# Sheet1.net
KiCad netlist of a schematic drawn in Altium Designer
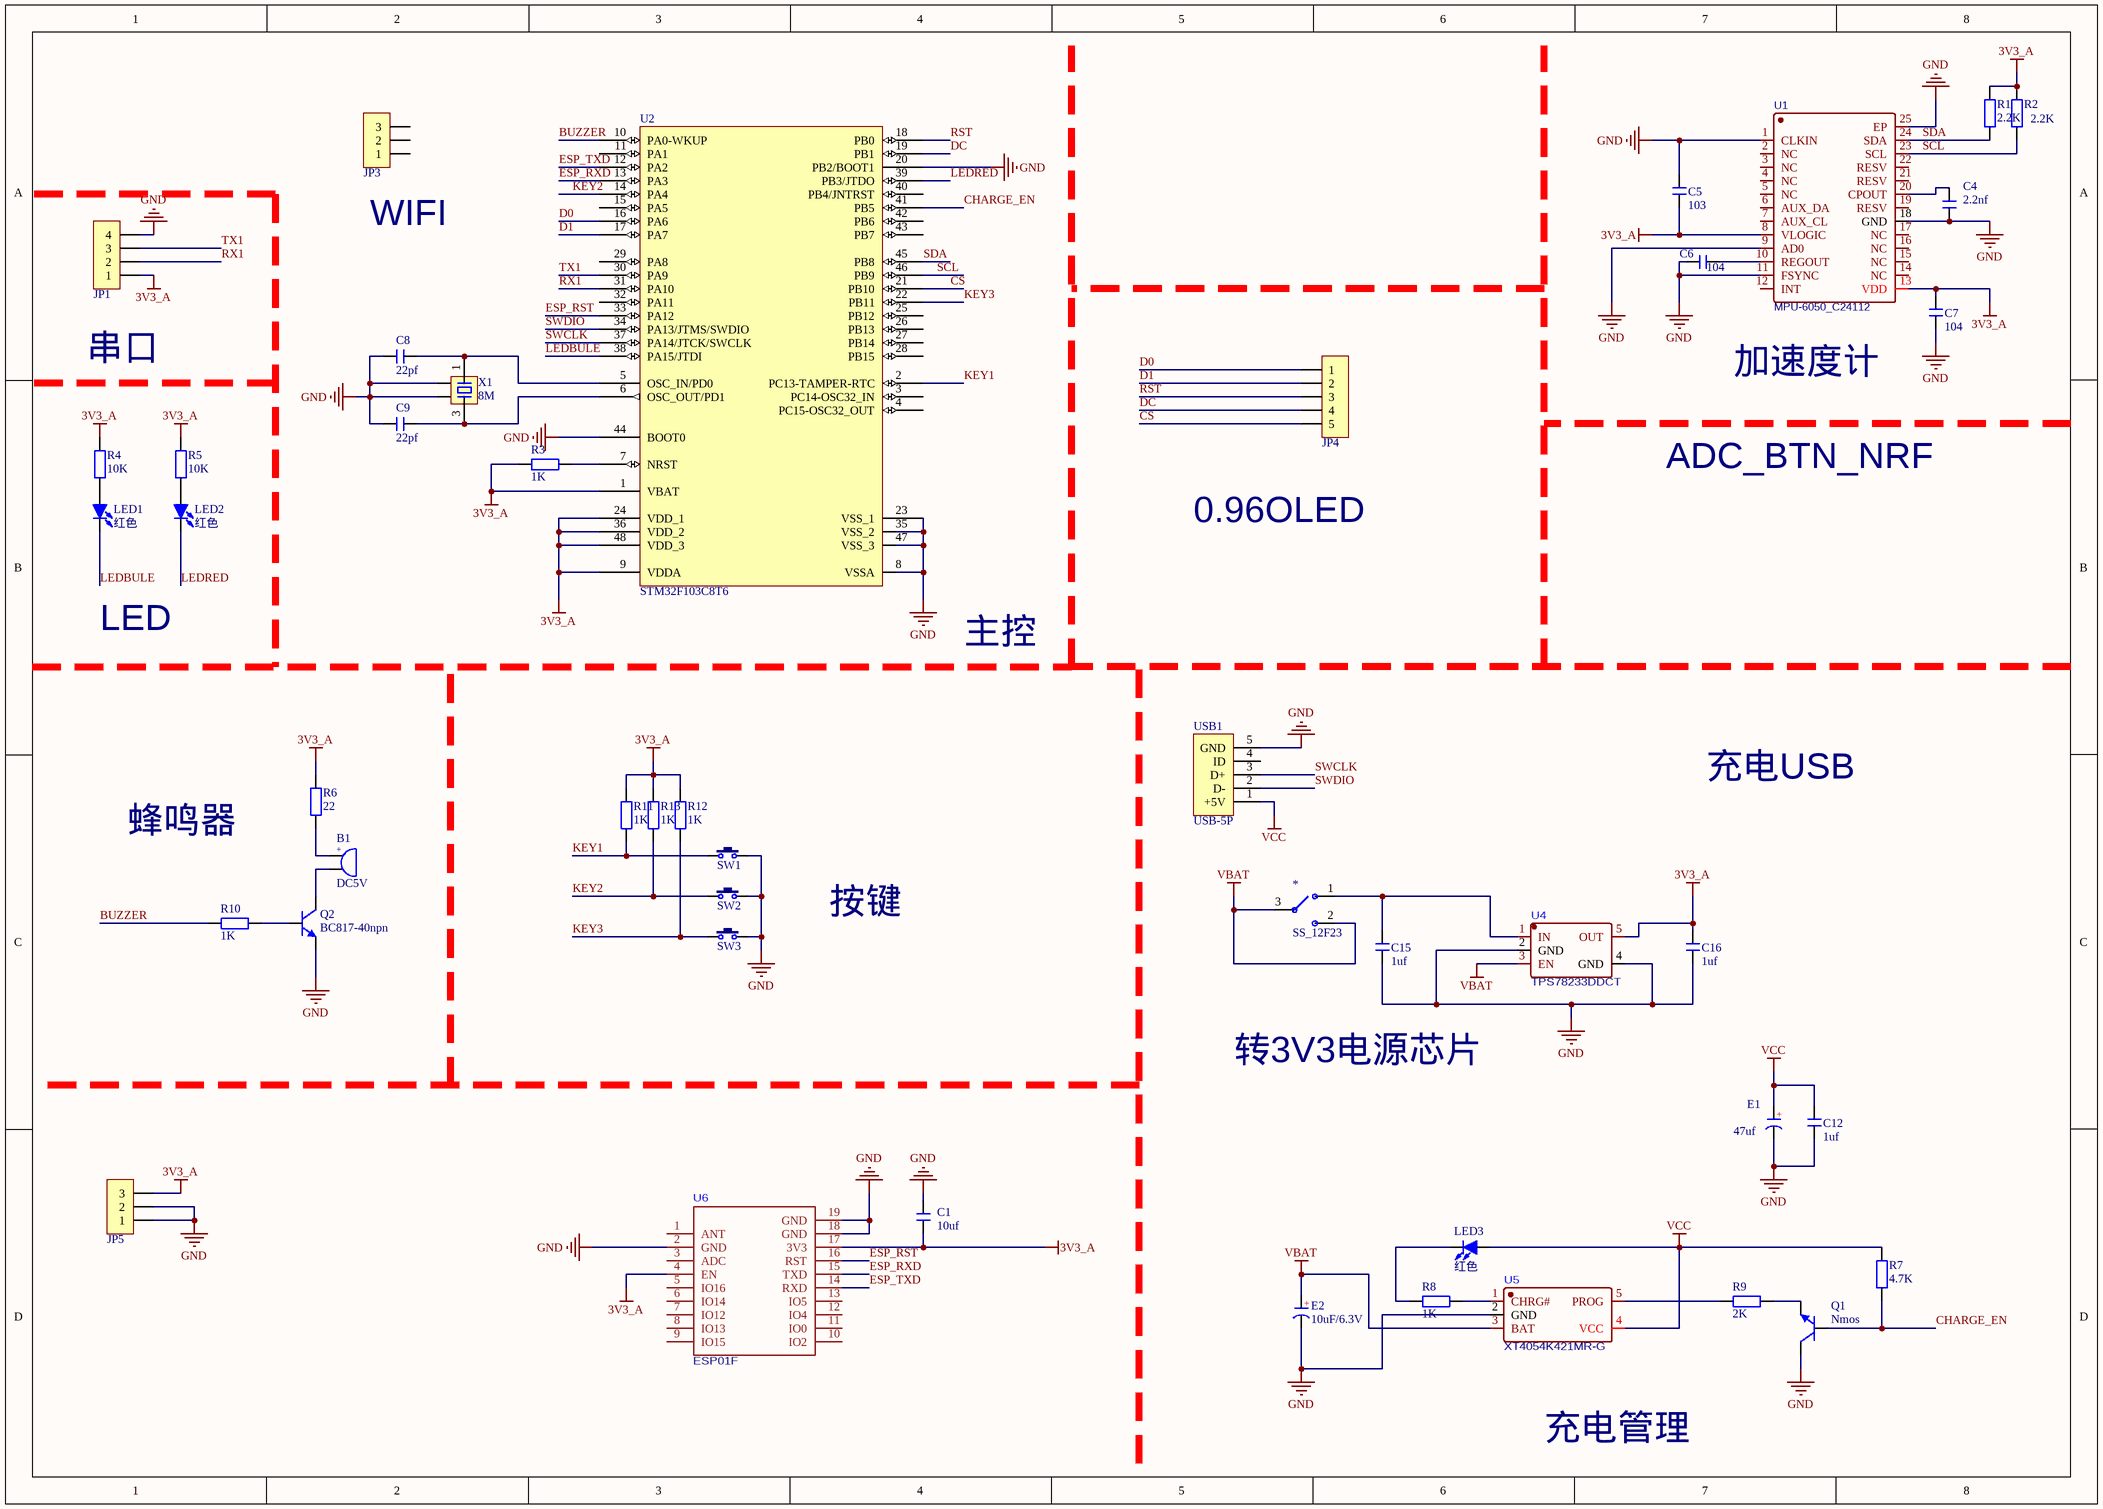
[diagram p0: Sheet1.SchDoc]

(export (version "E")
  (design (tool "Eeschema 10.0.6"))
  (components
    (comp (ref "*") (value "SS_12F23") (footprint "SS_12F23") (libsource (lib "Schlib1") (part "SS_12F23")))
    (comp (ref "B1")
      (value "DC5V")
      (footprint "蜂鸣器5020")
      (description "蜂鸣器")
      (fields (field (name "版权归属") "黎明电子style"))
      (libsource (lib "未分类器件") (part "BEEP"))
    )
    (comp (ref "C1")
      (value "10uf")
      (footprint "C 0805")
      (description "无极性贴片电容")
      (fields (field (name "版权归属") "黎明电子style"))
      (libsource (lib "电阻-电容-电感") (part "C"))
    )
    (comp (ref "C4")
      (value "2.2nf")
      (footprint "C 0603")
      (description "无极性贴片电容")
      (fields (field (name "版权归属") "黎明电子style"))
      (libsource (lib "电阻-电容-电感") (part "C"))
    )
    (comp (ref "C5")
      (value "103")
      (footprint "C 0603")
      (description "无极性贴片电容")
      (fields (field (name "版权归属") "黎明电子style"))
      (libsource (lib "电阻-电容-电感") (part "C"))
    )
    (comp (ref "C6")
      (value "104")
      (footprint "C 0603")
      (description "无极性贴片电容")
      (fields (field (name "版权归属") "黎明电子style"))
      (libsource (lib "电阻-电容-电感") (part "C"))
    )
    (comp (ref "C7")
      (value "104")
      (footprint "C 0603")
      (description "无极性贴片电容")
      (fields (field (name "版权归属") "黎明电子style"))
      (libsource (lib "电阻-电容-电感") (part "C"))
    )
    (comp (ref "C8")
      (value "22pf")
      (footprint "C 0603")
      (description "无极性贴片电容")
      (fields (field (name "版权归属") "黎明电子style"))
      (libsource (lib "电阻-电容-电感") (part "C"))
    )
    (comp (ref "C9")
      (value "22pf")
      (footprint "C 0603")
      (description "无极性贴片电容")
      (fields (field (name "版权归属") "黎明电子style"))
      (libsource (lib "电阻-电容-电感") (part "C"))
    )
    (comp (ref "C12")
      (value "1uf")
      (footprint "C 0603")
      (description "无极性贴片电容")
      (fields (field (name "版权归属") "黎明电子style"))
      (libsource (lib "电阻-电容-电感") (part "C"))
    )
    (comp (ref "C15")
      (value "1uf")
      (footprint "C 0603")
      (description "无极性贴片电容")
      (fields (field (name "版权归属") "黎明电子style"))
      (libsource (lib "电阻-电容-电感") (part "C"))
    )
    (comp (ref "C16")
      (value "1uf")
      (footprint "C 0603")
      (description "无极性贴片电容")
      (fields (field (name "版权归属") "黎明电子style"))
      (libsource (lib "电阻-电容-电感") (part "C"))
    )
    (comp (ref "E1")
      (value "47uf")
      (footprint "CD A(3216)")
      (description "贴片钽电容")
      (fields (field (name "版权归属") "黎明电子style"))
      (libsource (lib "电阻-电容-电感") (part "C-CD"))
    )
    (comp (ref "E2")
      (value "10uF/6.3V")
      (footprint "CD A(3216)")
      (description "贴片钽电容")
      (fields (field (name "版权归属") "黎明电子style"))
      (libsource (lib "电阻-电容-电感") (part "C-CD"))
    )
    (comp (ref "JP1")
      (value "HDR-1X4")
      (footprint "uart_pin")
      (description "4P接插件")
      (fields (field (name "版权归属") "黎明电子style"))
      (libsource (lib "接插件") (part "Header 4"))
    )
    (comp (ref "JP3")
      (value "HDR-1X3")
      (footprint "OLED_3PIN")
      (description "3P接插件")
      (fields (field (name "版权归属") "黎明电子style"))
      (libsource (lib "接插件") (part "Header 3"))
    )
    (comp (ref "JP4")
      (value "HDR-1X5")
      (footprint "OLED_5PIN")
      (description "5P接插件")
      (fields (field (name "版权归属") "黎明电子style"))
      (libsource (lib "接插件") (part "Header 5"))
    )
    (comp (ref "JP5")
      (value "HDR-1X3")
      (footprint "OLED_3PIN")
      (description "3P接插件")
      (fields (field (name "版权归属") "黎明电子style"))
      (libsource (lib "接插件") (part "Header 3"))
    )
    (comp (ref "LED1")
      (value "红色")
      (footprint "LED 0603G")
      (description "贴片LED")
      (fields (field (name "版权归属") "黎明电子style"))
      (libsource (lib "LED") (part "LED-SMD"))
    )
    (comp (ref "LED2")
      (value "红色")
      (footprint "LED 0603G")
      (description "贴片LED")
      (fields (field (name "版权归属") "黎明电子style"))
      (libsource (lib "LED") (part "LED-SMD"))
    )
    (comp (ref "LED3")
      (value "红色")
      (footprint "LED 0603G")
      (description "贴片LED")
      (fields (field (name "版权归属") "黎明电子style"))
      (libsource (lib "LED") (part "LED-SMD"))
    )
    (comp (ref "Q1")
      (value "Nmos")
      (footprint "NMOS")
      (description "低频放大-NPN型")
      (fields (field (name "版权归属") "黎明电子style"))
      (libsource (lib "三极管") (part "9013-SMD"))
    )
    (comp (ref "Q2")
      (value "BC817-40npn")
      (footprint "SOT23-3N")
      (description "高频放大-NPN型")
      (fields (field (name "版权归属") "黎明电子style"))
      (libsource (lib "三极管") (part "8050-SMD"))
    )
    (comp (ref "R1")
      (value "2.2K")
      (footprint "R 0603")
      (description "贴片电阻")
      (fields (field (name "版权归属") "黎明电子style"))
      (libsource (lib "电阻-电容-电感") (part "R"))
    )
    (comp (ref "R2")
      (value "2.2K")
      (footprint "R 0603")
      (description "贴片电阻")
      (fields (field (name "版权归属") "黎明电子style"))
      (libsource (lib "电阻-电容-电感") (part "R"))
    )
    (comp (ref "R3")
      (value "1K")
      (footprint "R 0603")
      (description "贴片电阻")
      (fields (field (name "版权归属") "黎明电子style"))
      (libsource (lib "电阻-电容-电感") (part "R"))
    )
    (comp (ref "R4")
      (value "10K")
      (footprint "R 0603")
      (description "贴片电阻")
      (fields (field (name "版权归属") "黎明电子style"))
      (libsource (lib "电阻-电容-电感") (part "R"))
    )
    (comp (ref "R5")
      (value "10K")
      (footprint "R 0603")
      (description "贴片电阻")
      (fields (field (name "版权归属") "黎明电子style"))
      (libsource (lib "电阻-电容-电感") (part "R"))
    )
    (comp (ref "R6")
      (value "22")
      (footprint "R 0603")
      (description "贴片电阻")
      (fields (field (name "版权归属") "黎明电子style"))
      (libsource (lib "电阻-电容-电感") (part "R"))
    )
    (comp (ref "R7")
      (value "4.7K")
      (footprint "R 0603")
      (description "贴片电阻")
      (fields (field (name "版权归属") "黎明电子style"))
      (libsource (lib "电阻-电容-电感") (part "R"))
    )
    (comp (ref "R8")
      (value "1K")
      (footprint "R 0603")
      (description "贴片电阻")
      (fields (field (name "版权归属") "黎明电子style"))
      (libsource (lib "电阻-电容-电感") (part "R"))
    )
    (comp (ref "R9")
      (value "2K")
      (footprint "R 0603")
      (description "贴片电阻")
      (fields (field (name "版权归属") "黎明电子style"))
      (libsource (lib "电阻-电容-电感") (part "R"))
    )
    (comp (ref "R10")
      (value "1K")
      (footprint "R 0603")
      (description "贴片电阻")
      (fields (field (name "版权归属") "黎明电子style"))
      (libsource (lib "电阻-电容-电感") (part "R"))
    )
    (comp (ref "R11")
      (value "1K")
      (footprint "R 0603")
      (description "贴片电阻")
      (fields (field (name "版权归属") "黎明电子style"))
      (libsource (lib "电阻-电容-电感") (part "R"))
    )
    (comp (ref "R12")
      (value "1K")
      (footprint "R 0603")
      (description "贴片电阻")
      (fields (field (name "版权归属") "黎明电子style"))
      (libsource (lib "电阻-电容-电感") (part "R"))
    )
    (comp (ref "R13")
      (value "1K")
      (footprint "R 0603")
      (description "贴片电阻")
      (fields (field (name "版权归属") "黎明电子style"))
      (libsource (lib "电阻-电容-电感") (part "R"))
    )
    (comp (ref "SW1")
      (value "3x6x5")
      (footprint "SB-2*4*3.5")
      (description "3x6轻触开关")
      (fields (field (name "版权归属") "黎明电子style"))
      (libsource (lib "按键-开关") (part "TSW 3x6"))
    )
    (comp (ref "SW2")
      (value "3x6x5")
      (footprint "SB-2*4*3.5")
      (description "3x6轻触开关")
      (fields (field (name "版权归属") "黎明电子style"))
      (libsource (lib "按键-开关") (part "TSW 3x6"))
    )
    (comp (ref "SW3")
      (value "3x6x5")
      (footprint "SB-2*4*3.5")
      (description "3x6轻触开关")
      (fields (field (name "版权归属") "黎明电子style"))
      (libsource (lib "按键-开关") (part "TSW 3x6"))
    )
    (comp (ref "U1")
      (value "MPU-6050_C24112")
      (footprint "MPU6050")
      (fields (field (name "BOM_MANUFACTURER PART") "MPU-6050") (field (name "BOM_SUPPLIER PART") "C24112"))
      (libsource (lib "PCB_Project") (part "MPU-6050_C24112"))
    )
    (comp (ref "U2")
      (value "STM32F103C8T6")
      (footprint "LQFP48 7X7_M")
      (description "Flaah:64/RAM:20/IO:36")
      (fields (field (name "版权归属") "黎明电子style"))
      (libsource (lib "STM32系列单片机") (part "STM32F103C8T6"))
    )
    (comp (ref "U4")
      (value "TPS78233DDCT")
      (footprint "SOT-23-5_L3.0-W1.7-P0.95-LS2.8-BR")
      (libsource (lib "Schlib1") (part "TPS78233DDCT"))
    )
    (comp (ref "U5")
      (value "XT4054K421MR-G")
      (footprint "SOT-23-5_L3.0-W1.7-P0.95-LS2.8-BR")
      (libsource (lib "Schlib1") (part "XT4054K421MR-G"))
    )
    (comp (ref "U6") (value "ESP01F") (footprint "ESP-01F") (libsource (lib "Schlib1") (part "ESP01F")))
    (comp (ref "USB1")
      (value "USB-5P")
      (footprint "MICRO-USB")
      (description "微型USB母座")
      (fields (field (name "版权归属") "黎明电子style"))
      (libsource (lib "接口类") (part "USB-5P"))
    )
    (comp (ref "X1")
      (value "8M")
      (footprint "OSC-SMD_4P-L3.2-W2.5-BL")
      (description "4脚晶振")
      (fields (field (name "版权归属") "源创客"))
      (libsource (lib "Schlib1") (part "XTAL-4"))
    )
  )
  (nets
    (net (code "1") (name "/BUZZER") (class "Default")
      (node (ref "R10") (pin "2") (pinfunction "2_2") (pintype "passive"))
      (node (ref "U2") (pin "10") (pinfunction "PA0-WKUP_10") (pintype "bidirectional"))
    )
    (net (code "2") (name "/CHARGE_EN") (class "Default")
      (node (ref "Q1") (pin "1") (pinfunction "B_1") (pintype "passive"))
      (node (ref "R7") (pin "2") (pinfunction "2_2") (pintype "passive"))
      (node (ref "U2") (pin "41") (pinfunction "PB5_41") (pintype "bidirectional"))
    )
    (net (code "3") (name "/CS") (class "Default")
      (node (ref "JP4") (pin "5") (pinfunction "5_5") (pintype "passive"))
      (node (ref "U2") (pin "21") (pinfunction "PB10_21") (pintype "bidirectional"))
    )
    (net (code "4") (name "/D0") (class "Default")
      (node (ref "JP4") (pin "1") (pinfunction "1_1") (pintype "passive"))
      (node (ref "U2") (pin "16") (pinfunction "PA6_16") (pintype "bidirectional"))
    )
    (net (code "5") (name "/D1") (class "Default")
      (node (ref "JP4") (pin "2") (pinfunction "2_2") (pintype "passive"))
      (node (ref "U2") (pin "17") (pinfunction "PA7_17") (pintype "bidirectional"))
    )
    (net (code "6") (name "/DC") (class "Default")
      (node (ref "JP4") (pin "4") (pinfunction "4_4") (pintype "passive"))
      (node (ref "U2") (pin "19") (pinfunction "PB1_19") (pintype "bidirectional"))
    )
    (net (code "7") (name "/ESP_RST") (class "Default")
      (node (ref "U2") (pin "33") (pinfunction "PA12_33") (pintype "bidirectional"))
      (node (ref "U6") (pin "16") (pinfunction "RST_16") (pintype "passive"))
    )
    (net (code "8") (name "/ESP_RXD") (class "Default")
      (node (ref "U2") (pin "13") (pinfunction "PA3_13") (pintype "bidirectional"))
      (node (ref "U6") (pin "15") (pinfunction "TXD_15") (pintype "passive"))
    )
    (net (code "9") (name "/ESP_TXD") (class "Default")
      (node (ref "U2") (pin "12") (pinfunction "PA2_12") (pintype "bidirectional"))
      (node (ref "U6") (pin "14") (pinfunction "RXD_14") (pintype "passive"))
    )
    (net (code "10") (name "/KEY1") (class "Default")
      (node (ref "R11") (pin "2") (pinfunction "2_2") (pintype "passive"))
      (node (ref "SW1") (pin "1") (pinfunction "1_1") (pintype "passive"))
      (node (ref "U2") (pin "2") (pinfunction "PC13-TAMPER-RTC_2") (pintype "bidirectional"))
    )
    (net (code "11") (name "/KEY2") (class "Default")
      (node (ref "R13") (pin "2") (pinfunction "2_2") (pintype "passive"))
      (node (ref "SW2") (pin "1") (pinfunction "1_1") (pintype "passive"))
      (node (ref "U2") (pin "14") (pinfunction "PA4_14") (pintype "bidirectional"))
    )
    (net (code "12") (name "/KEY3") (class "Default")
      (node (ref "R12") (pin "2") (pinfunction "2_2") (pintype "passive"))
      (node (ref "SW3") (pin "1") (pinfunction "1_1") (pintype "passive"))
      (node (ref "U2") (pin "22") (pinfunction "PB11_22") (pintype "bidirectional"))
    )
    (net (code "13") (name "/LEDBULE") (class "Default")
      (node (ref "LED1") (pin "2") (pinfunction "K_2") (pintype "passive"))
      (node (ref "U2") (pin "38") (pinfunction "PA15/JTDI_38") (pintype "bidirectional"))
    )
    (net (code "14") (name "/LEDRED") (class "Default")
      (node (ref "LED2") (pin "2") (pinfunction "K_2") (pintype "passive"))
      (node (ref "U2") (pin "39") (pinfunction "PB3/JTDO_39") (pintype "bidirectional"))
    )
    (net (code "15") (name "/RST") (class "Default")
      (node (ref "JP4") (pin "3") (pinfunction "3_3") (pintype "passive"))
      (node (ref "U2") (pin "18") (pinfunction "PB0_18") (pintype "bidirectional"))
    )
    (net (code "16") (name "/RX1") (class "Default")
      (node (ref "JP1") (pin "2") (pinfunction "2_2") (pintype "passive"))
      (node (ref "U2") (pin "31") (pinfunction "PA10_31") (pintype "bidirectional"))
    )
    (net (code "17") (name "/SCL") (class "Default")
      (node (ref "R2") (pin "1") (pinfunction "1_1") (pintype "passive"))
      (node (ref "U1") (pin "23") (pinfunction "SCL_23") (pintype "passive"))
      (node (ref "U2") (pin "46") (pinfunction "PB9_46") (pintype "bidirectional"))
    )
    (net (code "18") (name "/SDA") (class "Default")
      (node (ref "R1") (pin "1") (pinfunction "1_1") (pintype "passive"))
      (node (ref "U1") (pin "24") (pinfunction "SDA_24") (pintype "passive"))
      (node (ref "U2") (pin "45") (pinfunction "PB8_45") (pintype "bidirectional"))
    )
    (net (code "19") (name "/SWCLK") (class "Default")
      (node (ref "U2") (pin "37") (pinfunction "PA14/JTCK/SWCLK_37") (pintype "bidirectional"))
      (node (ref "USB1") (pin "3") (pinfunction "D+_3") (pintype "passive"))
    )
    (net (code "20") (name "/SWDIO") (class "Default")
      (node (ref "U2") (pin "34") (pinfunction "PA13/JTMS/SWDIO_34") (pintype "bidirectional"))
      (node (ref "USB1") (pin "2") (pinfunction "D-_2") (pintype "passive"))
    )
    (net (code "21") (name "/TX1") (class "Default")
      (node (ref "JP1") (pin "3") (pinfunction "3_3") (pintype "passive"))
      (node (ref "U2") (pin "30") (pinfunction "PA9_30") (pintype "bidirectional"))
    )
    (net (code "22") (name "3V3_A") (class "Default")
      (node (ref "C1") (pin "1") (pinfunction "1_1") (pintype "passive"))
      (node (ref "C16") (pin "2") (pinfunction "2_2") (pintype "passive"))
      (node (ref "C5") (pin "1") (pinfunction "1_1") (pintype "passive"))
      (node (ref "C7") (pin "2") (pinfunction "2_2") (pintype "passive"))
      (node (ref "JP1") (pin "1") (pinfunction "1_1") (pintype "passive"))
      (node (ref "JP5") (pin "3") (pinfunction "3_3") (pintype "passive"))
      (node (ref "R1") (pin "2") (pinfunction "2_2") (pintype "passive"))
      (node (ref "R11") (pin "1") (pinfunction "1_1") (pintype "passive"))
      (node (ref "R12") (pin "1") (pinfunction "1_1") (pintype "passive"))
      (node (ref "R13") (pin "1") (pinfunction "1_1") (pintype "passive"))
      (node (ref "R2") (pin "2") (pinfunction "2_2") (pintype "passive"))
      (node (ref "R3") (pin "2") (pinfunction "2_2") (pintype "passive"))
      (node (ref "R4") (pin "2") (pinfunction "2_2") (pintype "passive"))
      (node (ref "R5") (pin "2") (pinfunction "2_2") (pintype "passive"))
      (node (ref "R6") (pin "2") (pinfunction "2_2") (pintype "passive"))
      (node (ref "U1") (pin "13") (pinfunction "VDD_13") (pintype "passive"))
      (node (ref "U1") (pin "8") (pinfunction "VLOGIC_8") (pintype "passive"))
      (node (ref "U2") (pin "1") (pinfunction "VBAT_1") (pintype "power_in"))
      (node (ref "U2") (pin "24") (pinfunction "VDD_1_24") (pintype "power_in"))
      (node (ref "U2") (pin "36") (pinfunction "VDD_2_36") (pintype "power_in"))
      (node (ref "U2") (pin "48") (pinfunction "VDD_3_48") (pintype "power_in"))
      (node (ref "U2") (pin "9") (pinfunction "VDDA_9") (pintype "power_in"))
      (node (ref "U4") (pin "5") (pinfunction "OUT_5") (pintype "passive"))
      (node (ref "U6") (pin "17") (pinfunction "3V3_17") (pintype "passive"))
      (node (ref "U6") (pin "4") (pinfunction "EN_4") (pintype "passive"))
    )
    (net (code "23") (name "GND") (class "Default")
      (node (ref "C1") (pin "2") (pinfunction "2_2") (pintype "passive"))
      (node (ref "C12") (pin "1") (pinfunction "1_1") (pintype "passive"))
      (node (ref "C15") (pin "1") (pinfunction "1_1") (pintype "passive"))
      (node (ref "C16") (pin "1") (pinfunction "1_1") (pintype "passive"))
      (node (ref "C4") (pin "2") (pinfunction "2_2") (pintype "passive"))
      (node (ref "C5") (pin "2") (pinfunction "2_2") (pintype "passive"))
      (node (ref "C6") (pin "1") (pinfunction "1_1") (pintype "passive"))
      (node (ref "C7") (pin "1") (pinfunction "1_1") (pintype "passive"))
      (node (ref "C8") (pin "1") (pinfunction "1_1") (pintype "passive"))
      (node (ref "C9") (pin "1") (pinfunction "1_1") (pintype "passive"))
      (node (ref "E1") (pin "2") (pinfunction "K_2") (pintype "passive"))
      (node (ref "E2") (pin "2") (pinfunction "K_2") (pintype "passive"))
      (node (ref "JP1") (pin "4") (pinfunction "4_4") (pintype "passive"))
      (node (ref "JP5") (pin "1") (pinfunction "1_1") (pintype "passive"))
      (node (ref "JP5") (pin "2") (pinfunction "2_2") (pintype "passive"))
      (node (ref "Q1") (pin "3") (pinfunction "C_3") (pintype "passive"))
      (node (ref "Q2") (pin "2") (pinfunction "E_2") (pintype "passive"))
      (node (ref "SW1") (pin "2") (pinfunction "2_2") (pintype "passive"))
      (node (ref "SW2") (pin "2") (pinfunction "2_2") (pintype "passive"))
      (node (ref "SW3") (pin "2") (pinfunction "2_2") (pintype "passive"))
      (node (ref "U1") (pin "1") (pinfunction "CLKIN_1") (pintype "passive"))
      (node (ref "U1") (pin "11") (pinfunction "FSYNC_11") (pintype "passive"))
      (node (ref "U1") (pin "18") (pinfunction "GND_18") (pintype "passive"))
      (node (ref "U1") (pin "25") (pinfunction "EP_25") (pintype "passive"))
      (node (ref "U1") (pin "9") (pinfunction "AD0_9") (pintype "passive"))
      (node (ref "U2") (pin "20") (pinfunction "PB2/BOOT1_20") (pintype "passive"))
      (node (ref "U2") (pin "23") (pinfunction "VSS_1_23") (pintype "power_in"))
      (node (ref "U2") (pin "35") (pinfunction "VSS_2_35") (pintype "power_in"))
      (node (ref "U2") (pin "44") (pinfunction "BOOT0_44") (pintype "passive"))
      (node (ref "U2") (pin "47") (pinfunction "VSS_3_47") (pintype "power_in"))
      (node (ref "U2") (pin "8") (pinfunction "VSSA_8") (pintype "power_in"))
      (node (ref "U4") (pin "2") (pinfunction "GND_2") (pintype "passive"))
      (node (ref "U4") (pin "4") (pinfunction "GND_4") (pintype "passive"))
      (node (ref "U5") (pin "2") (pinfunction "GND_2") (pintype "passive"))
      (node (ref "U6") (pin "18") (pinfunction "GND_18") (pintype "passive"))
      (node (ref "U6") (pin "19") (pinfunction "GND_19") (pintype "passive"))
      (node (ref "U6") (pin "2") (pinfunction "GND_2") (pintype "passive"))
      (node (ref "USB1") (pin "5") (pinfunction "GND_5") (pintype "passive"))
      (node (ref "X1") (pin "2") (pinfunction "2_2") (pintype "passive"))
      (node (ref "X1") (pin "4") (pinfunction "4_4") (pintype "passive"))
    )
    (net (code "24") (name "Net-(B1-Pad1)") (class "Default")
      (node (ref "B1") (pin "1") (pinfunction "1_1") (pintype "passive"))
      (node (ref "R6") (pin "1") (pinfunction "1_1") (pintype "passive"))
    )
    (net (code "25") (name "Net-(LED1-A)") (class "Default")
      (node (ref "LED1") (pin "1") (pinfunction "A_1") (pintype "passive"))
      (node (ref "R4") (pin "1") (pinfunction "1_1") (pintype "passive"))
    )
    (net (code "26") (name "Net-(LED2-A)") (class "Default")
      (node (ref "LED2") (pin "1") (pinfunction "A_1") (pintype "passive"))
      (node (ref "R5") (pin "1") (pinfunction "1_1") (pintype "passive"))
    )
    (net (code "27") (name "Net-(LED3-K)") (class "Default")
      (node (ref "LED3") (pin "2") (pinfunction "K_2") (pintype "passive"))
      (node (ref "R8") (pin "2") (pinfunction "2_2") (pintype "passive"))
    )
    (net (code "28") (name "Net-(Q1-E)") (class "Default")
      (node (ref "Q1") (pin "2") (pinfunction "E_2") (pintype "passive"))
      (node (ref "R9") (pin "1") (pinfunction "1_1") (pintype "passive"))
    )
    (net (code "29") (name "Net-(Q2-B)") (class "Default")
      (node (ref "Q2") (pin "1") (pinfunction "B_1") (pintype "passive"))
      (node (ref "R10") (pin "1") (pinfunction "1_1") (pintype "passive"))
    )
    (net (code "30") (name "Net-(Q2-C)") (class "Default")
      (node (ref "B1") (pin "2") (pinfunction "2_2") (pintype "passive"))
      (node (ref "Q2") (pin "3") (pinfunction "C_3") (pintype "passive"))
    )
    (net (code "31") (name "Net-(U1-CPOUT)") (class "Default")
      (node (ref "C4") (pin "1") (pinfunction "1_1") (pintype "passive"))
      (node (ref "U1") (pin "20") (pinfunction "CPOUT_20") (pintype "passive"))
    )
    (net (code "32") (name "Net-(U1-REGOUT)") (class "Default")
      (node (ref "C6") (pin "2") (pinfunction "2_2") (pintype "passive"))
      (node (ref "U1") (pin "10") (pinfunction "REGOUT_10") (pintype "passive"))
    )
    (net (code "33") (name "Net-(U2-NRST)") (class "Default")
      (node (ref "R3") (pin "1") (pinfunction "1_1") (pintype "passive"))
      (node (ref "U2") (pin "7") (pinfunction "NRST_7") (pintype "bidirectional"))
    )
    (net (code "34") (name "Net-(U2-OSC_IN{slash}PD0)") (class "Default")
      (node (ref "C8") (pin "2") (pinfunction "2_2") (pintype "passive"))
      (node (ref "U2") (pin "5") (pinfunction "OSC_IN/PD0_5") (pintype "passive"))
      (node (ref "X1") (pin "1") (pinfunction "1_1") (pintype "passive"))
    )
    (net (code "35") (name "Net-(U2-OSC_OUT{slash}PD1)") (class "Default")
      (node (ref "C9") (pin "2") (pinfunction "2_2") (pintype "passive"))
      (node (ref "U2") (pin "6") (pinfunction "OSC_OUT/PD1_6") (pintype "output"))
      (node (ref "X1") (pin "3") (pinfunction "3_3") (pintype "passive"))
    )
    (net (code "36") (name "Net-(U4-IN)") (class "Default")
      (node (ref "*") (pin "1") (pinfunction "1_1") (pintype "passive"))
      (node (ref "C15") (pin "2") (pinfunction "2_2") (pintype "passive"))
      (node (ref "U4") (pin "1") (pinfunction "IN_1") (pintype "passive"))
    )
    (net (code "37") (name "Net-(U5-CHRG#)") (class "Default")
      (node (ref "R8") (pin "1") (pinfunction "1_1") (pintype "passive"))
      (node (ref "U5") (pin "1") (pinfunction "CHRG#_1") (pintype "passive"))
    )
    (net (code "38") (name "Net-(U5-PROG)") (class "Default")
      (node (ref "R9") (pin "2") (pinfunction "2_2") (pintype "passive"))
      (node (ref "U5") (pin "5") (pinfunction "PROG_5") (pintype "passive"))
    )
    (net (code "39") (name "VBAT") (class "Default")
      (node (ref "*") (pin "2") (pinfunction "2_2") (pintype "passive"))
      (node (ref "*") (pin "3") (pinfunction "3_3") (pintype "passive"))
      (node (ref "E2") (pin "1") (pinfunction "A_1") (pintype "passive"))
      (node (ref "U4") (pin "3") (pinfunction "EN_3") (pintype "passive"))
      (node (ref "U5") (pin "3") (pinfunction "BAT_3") (pintype "passive"))
    )
    (net (code "40") (name "VCC") (class "Default")
      (node (ref "C12") (pin "2") (pinfunction "2_2") (pintype "passive"))
      (node (ref "E1") (pin "1") (pinfunction "A_1") (pintype "passive"))
      (node (ref "LED3") (pin "1") (pinfunction "A_1") (pintype "passive"))
      (node (ref "R7") (pin "1") (pinfunction "1_1") (pintype "passive"))
      (node (ref "U5") (pin "4") (pinfunction "VCC_4") (pintype "passive"))
      (node (ref "USB1") (pin "1") (pinfunction "+5V_1") (pintype "passive"))
    )
    (net (code "41") (name "unconnected-(JP3-Pad1)") (class "Default")
      (node (ref "JP3") (pin "1") (pinfunction "1_1") (pintype "passive"))
    )
    (net (code "42") (name "unconnected-(JP3-Pad2)") (class "Default")
      (node (ref "JP3") (pin "2") (pinfunction "2_2") (pintype "passive"))
    )
    (net (code "43") (name "unconnected-(JP3-Pad3)") (class "Default")
      (node (ref "JP3") (pin "3") (pinfunction "3_3") (pintype "passive"))
    )
    (net (code "44") (name "unconnected-(U1-AUX_CL-Pad7)") (class "Default")
      (node (ref "U1") (pin "7") (pinfunction "AUX_CL_7") (pintype "passive"))
    )
    (net (code "45") (name "unconnected-(U1-AUX_DA-Pad6)") (class "Default")
      (node (ref "U1") (pin "6") (pinfunction "AUX_DA_6") (pintype "passive"))
    )
    (net (code "46") (name "unconnected-(U1-INT-Pad12)") (class "Default")
      (node (ref "U1") (pin "12") (pinfunction "INT_12") (pintype "passive"))
    )
    (net (code "47") (name "unconnected-(U1-NC-Pad2)") (class "Default")
      (node (ref "U1") (pin "2") (pinfunction "NC_2") (pintype "passive"))
    )
    (net (code "48") (name "unconnected-(U1-NC-Pad3)") (class "Default")
      (node (ref "U1") (pin "3") (pinfunction "NC_3") (pintype "passive"))
    )
    (net (code "49") (name "unconnected-(U1-NC-Pad4)") (class "Default")
      (node (ref "U1") (pin "4") (pinfunction "NC_4") (pintype "passive"))
    )
    (net (code "50") (name "unconnected-(U1-NC-Pad5)") (class "Default")
      (node (ref "U1") (pin "5") (pinfunction "NC_5") (pintype "passive"))
    )
    (net (code "51") (name "unconnected-(U1-NC-Pad14)") (class "Default")
      (node (ref "U1") (pin "14") (pinfunction "NC_14") (pintype "passive"))
    )
    (net (code "52") (name "unconnected-(U1-NC-Pad15)") (class "Default")
      (node (ref "U1") (pin "15") (pinfunction "NC_15") (pintype "passive"))
    )
    (net (code "53") (name "unconnected-(U1-NC-Pad16)") (class "Default")
      (node (ref "U1") (pin "16") (pinfunction "NC_16") (pintype "passive"))
    )
    (net (code "54") (name "unconnected-(U1-NC-Pad17)") (class "Default")
      (node (ref "U1") (pin "17") (pinfunction "NC_17") (pintype "passive"))
    )
    (net (code "55") (name "unconnected-(U1-RESV-Pad19)") (class "Default")
      (node (ref "U1") (pin "19") (pinfunction "RESV_19") (pintype "passive"))
    )
    (net (code "56") (name "unconnected-(U1-RESV-Pad21)") (class "Default")
      (node (ref "U1") (pin "21") (pinfunction "RESV_21") (pintype "passive"))
    )
    (net (code "57") (name "unconnected-(U1-RESV-Pad22)") (class "Default")
      (node (ref "U1") (pin "22") (pinfunction "RESV_22") (pintype "passive"))
    )
    (net (code "58") (name "unconnected-(U2-PA1-Pad11)") (class "Default")
      (node (ref "U2") (pin "11") (pinfunction "PA1_11") (pintype "bidirectional"))
    )
    (net (code "59") (name "unconnected-(U2-PA5-Pad15)") (class "Default")
      (node (ref "U2") (pin "15") (pinfunction "PA5_15") (pintype "bidirectional"))
    )
    (net (code "60") (name "unconnected-(U2-PA8-Pad29)") (class "Default")
      (node (ref "U2") (pin "29") (pinfunction "PA8_29") (pintype "bidirectional"))
    )
    (net (code "61") (name "unconnected-(U2-PA11-Pad32)") (class "Default")
      (node (ref "U2") (pin "32") (pinfunction "PA11_32") (pintype "bidirectional"))
    )
    (net (code "62") (name "unconnected-(U2-PB4{slash}JNTRST-Pad40)") (class "Default")
      (node (ref "U2") (pin "40") (pinfunction "PB4/JNTRST_40") (pintype "bidirectional"))
    )
    (net (code "63") (name "unconnected-(U2-PB6-Pad42)") (class "Default")
      (node (ref "U2") (pin "42") (pinfunction "PB6_42") (pintype "bidirectional"))
    )
    (net (code "64") (name "unconnected-(U2-PB7-Pad43)") (class "Default")
      (node (ref "U2") (pin "43") (pinfunction "PB7_43") (pintype "bidirectional"))
    )
    (net (code "65") (name "unconnected-(U2-PB12-Pad25)") (class "Default")
      (node (ref "U2") (pin "25") (pinfunction "PB12_25") (pintype "bidirectional"))
    )
    (net (code "66") (name "unconnected-(U2-PB13-Pad26)") (class "Default")
      (node (ref "U2") (pin "26") (pinfunction "PB13_26") (pintype "bidirectional"))
    )
    (net (code "67") (name "unconnected-(U2-PB14-Pad27)") (class "Default")
      (node (ref "U2") (pin "27") (pinfunction "PB14_27") (pintype "bidirectional"))
    )
    (net (code "68") (name "unconnected-(U2-PB15-Pad28)") (class "Default")
      (node (ref "U2") (pin "28") (pinfunction "PB15_28") (pintype "bidirectional"))
    )
    (net (code "69") (name "unconnected-(U2-PC14-OSC32_IN-Pad3)") (class "Default")
      (node (ref "U2") (pin "3") (pinfunction "PC14-OSC32_IN_3") (pintype "bidirectional"))
    )
    (net (code "70") (name "unconnected-(U2-PC15-OSC32_OUT-Pad4)") (class "Default")
      (node (ref "U2") (pin "4") (pinfunction "PC15-OSC32_OUT_4") (pintype "bidirectional"))
    )
    (net (code "71") (name "unconnected-(U6-ADC-Pad3)") (class "Default")
      (node (ref "U6") (pin "3") (pinfunction "ADC_3") (pintype "passive"))
    )
    (net (code "72") (name "unconnected-(U6-ANT-Pad1)") (class "Default")
      (node (ref "U6") (pin "1") (pinfunction "ANT_1") (pintype "passive"))
    )
    (net (code "73") (name "unconnected-(U6-IO0-Pad11)") (class "Default")
      (node (ref "U6") (pin "11") (pinfunction "IO0_11") (pintype "passive"))
    )
    (net (code "74") (name "unconnected-(U6-IO2-Pad10)") (class "Default")
      (node (ref "U6") (pin "10") (pinfunction "IO2_10") (pintype "passive"))
    )
    (net (code "75") (name "unconnected-(U6-IO4-Pad12)") (class "Default")
      (node (ref "U6") (pin "12") (pinfunction "IO4_12") (pintype "passive"))
    )
    (net (code "76") (name "unconnected-(U6-IO5-Pad13)") (class "Default")
      (node (ref "U6") (pin "13") (pinfunction "IO5_13") (pintype "passive"))
    )
    (net (code "77") (name "unconnected-(U6-IO12-Pad7)") (class "Default")
      (node (ref "U6") (pin "7") (pinfunction "IO12_7") (pintype "passive"))
    )
    (net (code "78") (name "unconnected-(U6-IO13-Pad8)") (class "Default")
      (node (ref "U6") (pin "8") (pinfunction "IO13_8") (pintype "passive"))
    )
    (net (code "79") (name "unconnected-(U6-IO14-Pad6)") (class "Default")
      (node (ref "U6") (pin "6") (pinfunction "IO14_6") (pintype "passive"))
    )
    (net (code "80") (name "unconnected-(U6-IO15-Pad9)") (class "Default")
      (node (ref "U6") (pin "9") (pinfunction "IO15_9") (pintype "passive"))
    )
    (net (code "81") (name "unconnected-(U6-IO16-Pad5)") (class "Default")
      (node (ref "U6") (pin "5") (pinfunction "IO16_5") (pintype "passive"))
    )
    (net (code "82") (name "unconnected-(USB1-ID-Pad4)") (class "Default")
      (node (ref "USB1") (pin "4") (pinfunction "ID_4") (pintype "passive"))
    )
  )
)
